# CUTTER.net
KiCad netlist of a schematic drawn in EAGLE
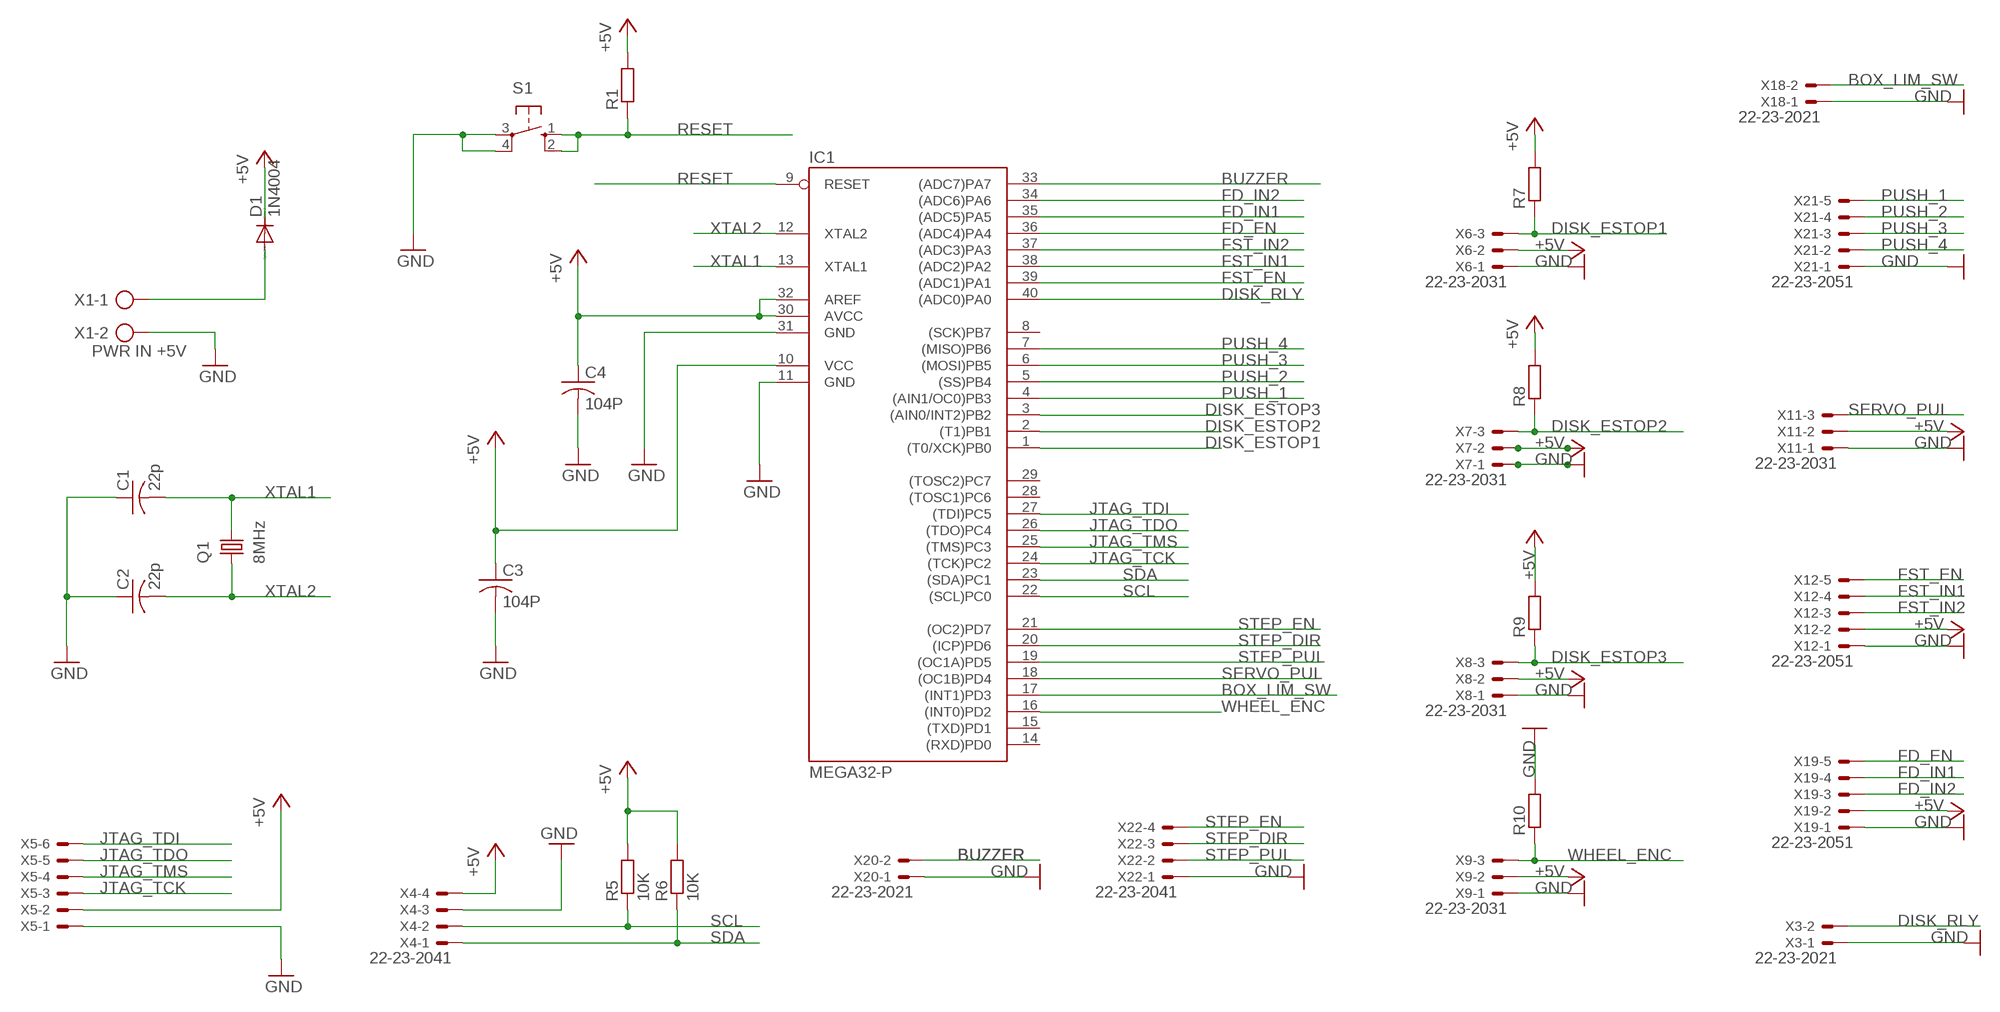
[diagram p0: schematic, sheet 1]

(export (version "E")
  (design (tool "Eeschema 10.0.6"))
  (components
    (comp (ref "C1")
      (value "22p")
      (footprint "eagle-import:C025-025X050")
      (libsource (lib "eagle-import") (part "C-US025-025X050"))
    )
    (comp (ref "C2")
      (value "22p")
      (footprint "eagle-import:C025-025X050")
      (libsource (lib "eagle-import") (part "C-US025-025X050"))
    )
    (comp (ref "C3")
      (value "104P")
      (footprint "eagle-import:C025-025X050")
      (libsource (lib "eagle-import") (part "C-US025-025X050"))
    )
    (comp (ref "C4")
      (value "104P")
      (footprint "eagle-import:C025-025X050")
      (libsource (lib "eagle-import") (part "C-US025-025X050"))
    )
    (comp (ref "D1")
      (value "1N4004")
      (footprint "eagle-import:DO41-10")
      (libsource (lib "eagle-import") (part "1N4004"))
    )
    (comp (ref "IC1")
      (value "MEGA32-P")
      (footprint "eagle-import:DIL40")
      (fields (field (name "MPN") "ATMEGA32-16PU"))
      (libsource (lib "eagle-import") (part "MEGA32-P"))
    )
    (comp (ref "Q1")
      (value "8MHz")
      (footprint "eagle-import:HC49_S")
      (libsource (lib "eagle-import") (part "CRYSTALHC49S"))
    )
    (comp (ref "R1")
      (value "R-EU_0207/10")
      (footprint "eagle-import:0207_10")
      (libsource (lib "eagle-import") (part "R-EU_0207/10"))
    )
    (comp (ref "R5")
      (value "10K")
      (footprint "eagle-import:0207_10")
      (libsource (lib "eagle-import") (part "R-EU_0207/10"))
    )
    (comp (ref "R6")
      (value "10K")
      (footprint "eagle-import:0207_10")
      (libsource (lib "eagle-import") (part "R-EU_0207/10"))
    )
    (comp (ref "R7")
      (value "R-EU_0207/10")
      (footprint "eagle-import:0207_10")
      (libsource (lib "eagle-import") (part "R-EU_0207/10"))
    )
    (comp (ref "R8")
      (value "R-EU_0207/10")
      (footprint "eagle-import:0207_10")
      (libsource (lib "eagle-import") (part "R-EU_0207/10"))
    )
    (comp (ref "R9")
      (value "R-EU_0207/10")
      (footprint "eagle-import:0207_10")
      (libsource (lib "eagle-import") (part "R-EU_0207/10"))
    )
    (comp (ref "R10")
      (value "R-EU_0207/10")
      (footprint "eagle-import:0207_10")
      (libsource (lib "eagle-import") (part "R-EU_0207/10"))
    )
    (comp (ref "S1")
      (value "10-XX")
      (footprint "eagle-import:B3F-10XX")
      (fields (field (name "MPN") "B3F-1000"))
      (libsource (lib "eagle-import") (part "10-XX"))
    )
    (comp (ref "X1")
      (value "PWR IN +5V")
      (footprint "eagle-import:AK500_2")
      (fields (field (name "SPICEPREFIX") "X"))
      (libsource (lib "eagle-import") (part "AK500/2"))
    )
    (comp (ref "X3")
      (value "22-23-2021")
      (footprint "eagle-import:22-23-2021")
      (fields (field (name "MF") "MOLEX"))
      (libsource (lib "eagle-import") (part "22-23-2021"))
    )
    (comp (ref "X4")
      (value "22-23-2041")
      (footprint "eagle-import:22-23-2041")
      (fields (field (name "MF") "MOLEX"))
      (libsource (lib "eagle-import") (part "22-23-2041"))
    )
    (comp (ref "X5")
      (value "22-23-2061")
      (footprint "eagle-import:22-23-2061")
      (fields (field (name "MF") "MOLEX"))
      (libsource (lib "eagle-import") (part "22-23-2061"))
    )
    (comp (ref "X6")
      (value "22-23-2031")
      (footprint "eagle-import:22-23-2031")
      (fields (field (name "MF") "MOLEX"))
      (libsource (lib "eagle-import") (part "22-23-2031"))
    )
    (comp (ref "X7")
      (value "22-23-2031")
      (footprint "eagle-import:22-23-2031")
      (fields (field (name "MF") "MOLEX"))
      (libsource (lib "eagle-import") (part "22-23-2031"))
    )
    (comp (ref "X8")
      (value "22-23-2031")
      (footprint "eagle-import:22-23-2031")
      (fields (field (name "MF") "MOLEX"))
      (libsource (lib "eagle-import") (part "22-23-2031"))
    )
    (comp (ref "X9")
      (value "22-23-2031")
      (footprint "eagle-import:22-23-2031")
      (fields (field (name "MF") "MOLEX"))
      (libsource (lib "eagle-import") (part "22-23-2031"))
    )
    (comp (ref "X11")
      (value "22-23-2031")
      (footprint "eagle-import:22-23-2031")
      (fields (field (name "MF") "MOLEX"))
      (libsource (lib "eagle-import") (part "22-23-2031"))
    )
    (comp (ref "X12")
      (value "22-23-2051")
      (footprint "eagle-import:22-23-2051")
      (fields (field (name "MF") "MOLEX"))
      (libsource (lib "eagle-import") (part "22-23-2051"))
    )
    (comp (ref "X18")
      (value "22-23-2021")
      (footprint "eagle-import:22-23-2021")
      (fields (field (name "MF") "MOLEX"))
      (libsource (lib "eagle-import") (part "22-23-2021"))
    )
    (comp (ref "X19")
      (value "22-23-2051")
      (footprint "eagle-import:22-23-2051")
      (fields (field (name "MF") "MOLEX"))
      (libsource (lib "eagle-import") (part "22-23-2051"))
    )
    (comp (ref "X20")
      (value "22-23-2021")
      (footprint "eagle-import:22-23-2021")
      (fields (field (name "MF") "MOLEX"))
      (libsource (lib "eagle-import") (part "22-23-2021"))
    )
    (comp (ref "X21")
      (value "22-23-2051")
      (footprint "eagle-import:22-23-2051")
      (fields (field (name "MF") "MOLEX"))
      (libsource (lib "eagle-import") (part "22-23-2051"))
    )
    (comp (ref "X22")
      (value "22-23-2041")
      (footprint "eagle-import:22-23-2041")
      (fields (field (name "MF") "MOLEX"))
      (libsource (lib "eagle-import") (part "22-23-2041"))
    )
  )
  (nets
    (net (code "1") (name "+5V") (class "Default")
      (node (ref "C3") (pin "1") (pinfunction "1_1") (pintype "passive"))
      (node (ref "C4") (pin "1") (pinfunction "1_1") (pintype "passive"))
      (node (ref "D1") (pin "C") (pinfunction "C_C") (pintype "passive"))
      (node (ref "IC1") (pin "10") (pinfunction "VCC_10") (pintype "power_in"))
      (node (ref "IC1") (pin "30") (pinfunction "AVCC_30") (pintype "power_in"))
      (node (ref "IC1") (pin "32") (pinfunction "AREF_32") (pintype "passive"))
      (node (ref "R1") (pin "2") (pinfunction "2_2") (pintype "passive"))
      (node (ref "R5") (pin "2") (pinfunction "2_2") (pintype "passive"))
      (node (ref "R6") (pin "2") (pinfunction "2_2") (pintype "passive"))
      (node (ref "R7") (pin "2") (pinfunction "2_2") (pintype "passive"))
      (node (ref "R8") (pin "2") (pinfunction "2_2") (pintype "passive"))
      (node (ref "R9") (pin "2") (pinfunction "2_2") (pintype "passive"))
      (node (ref "X11") (pin "2") (pinfunction "S_2") (pintype "passive"))
      (node (ref "X12") (pin "2") (pinfunction "S_2") (pintype "passive"))
      (node (ref "X19") (pin "2") (pinfunction "S_2") (pintype "passive"))
      (node (ref "X4") (pin "4") (pinfunction "S_4") (pintype "passive"))
      (node (ref "X5") (pin "2") (pinfunction "S_2") (pintype "passive"))
      (node (ref "X6") (pin "2") (pinfunction "S_2") (pintype "passive"))
      (node (ref "X7") (pin "2") (pinfunction "S_2") (pintype "passive"))
      (node (ref "X8") (pin "2") (pinfunction "S_2") (pintype "passive"))
      (node (ref "X9") (pin "2") (pinfunction "S_2") (pintype "passive"))
    )
    (net (code "2") (name "/BOX_LIM_SW") (class "Default")
      (node (ref "IC1") (pin "17") (pinfunction "(INT1)PD3_17") (pintype "bidirectional"))
      (node (ref "X18") (pin "2") (pinfunction "S_2") (pintype "passive"))
    )
    (net (code "3") (name "/BUZZER") (class "Default")
      (node (ref "IC1") (pin "33") (pinfunction "(ADC7)PA7_33") (pintype "bidirectional"))
      (node (ref "X20") (pin "2") (pinfunction "S_2") (pintype "passive"))
    )
    (net (code "4") (name "/DISK_ESTOP1") (class "Default")
      (node (ref "IC1") (pin "1") (pinfunction "(T0/XCK)PB0_1") (pintype "bidirectional"))
      (node (ref "R7") (pin "1") (pinfunction "1_1") (pintype "passive"))
      (node (ref "X6") (pin "3") (pinfunction "S_3") (pintype "passive"))
    )
    (net (code "5") (name "/DISK_ESTOP2") (class "Default")
      (node (ref "IC1") (pin "2") (pinfunction "(T1)PB1_2") (pintype "bidirectional"))
      (node (ref "R8") (pin "1") (pinfunction "1_1") (pintype "passive"))
      (node (ref "X7") (pin "3") (pinfunction "S_3") (pintype "passive"))
    )
    (net (code "6") (name "/DISK_ESTOP3") (class "Default")
      (node (ref "IC1") (pin "3") (pinfunction "(AIN0/INT2)PB2_3") (pintype "bidirectional"))
      (node (ref "R9") (pin "1") (pinfunction "1_1") (pintype "passive"))
      (node (ref "X8") (pin "3") (pinfunction "S_3") (pintype "passive"))
    )
    (net (code "7") (name "/DISK_RLY") (class "Default")
      (node (ref "IC1") (pin "40") (pinfunction "(ADC0)PA0_40") (pintype "bidirectional"))
      (node (ref "X3") (pin "2") (pinfunction "S_2") (pintype "passive"))
    )
    (net (code "8") (name "/FD_EN") (class "Default")
      (node (ref "IC1") (pin "36") (pinfunction "(ADC4)PA4_36") (pintype "bidirectional"))
      (node (ref "X19") (pin "5") (pinfunction "S_5") (pintype "passive"))
    )
    (net (code "9") (name "/FD_IN1") (class "Default")
      (node (ref "IC1") (pin "35") (pinfunction "(ADC5)PA5_35") (pintype "bidirectional"))
      (node (ref "X19") (pin "4") (pinfunction "S_4") (pintype "passive"))
    )
    (net (code "10") (name "/FD_IN2") (class "Default")
      (node (ref "IC1") (pin "34") (pinfunction "(ADC6)PA6_34") (pintype "bidirectional"))
      (node (ref "X19") (pin "3") (pinfunction "S_3") (pintype "passive"))
    )
    (net (code "11") (name "/FST_EN") (class "Default")
      (node (ref "IC1") (pin "39") (pinfunction "(ADC1)PA1_39") (pintype "bidirectional"))
      (node (ref "X12") (pin "5") (pinfunction "S_5") (pintype "passive"))
    )
    (net (code "12") (name "/FST_IN1") (class "Default")
      (node (ref "IC1") (pin "38") (pinfunction "(ADC2)PA2_38") (pintype "bidirectional"))
      (node (ref "X12") (pin "4") (pinfunction "S_4") (pintype "passive"))
    )
    (net (code "13") (name "/FST_IN2") (class "Default")
      (node (ref "IC1") (pin "37") (pinfunction "(ADC3)PA3_37") (pintype "bidirectional"))
      (node (ref "X12") (pin "3") (pinfunction "S_3") (pintype "passive"))
    )
    (net (code "14") (name "/JTAG_TCK") (class "Default")
      (node (ref "IC1") (pin "24") (pinfunction "(TCK)PC2_24") (pintype "bidirectional"))
      (node (ref "X5") (pin "3") (pinfunction "S_3") (pintype "passive"))
    )
    (net (code "15") (name "/JTAG_TDI") (class "Default")
      (node (ref "IC1") (pin "27") (pinfunction "(TDI)PC5_27") (pintype "bidirectional"))
      (node (ref "X5") (pin "6") (pinfunction "S_6") (pintype "passive"))
    )
    (net (code "16") (name "/JTAG_TDO") (class "Default")
      (node (ref "IC1") (pin "26") (pinfunction "(TDO)PC4_26") (pintype "bidirectional"))
      (node (ref "X5") (pin "5") (pinfunction "S_5") (pintype "passive"))
    )
    (net (code "17") (name "/JTAG_TMS") (class "Default")
      (node (ref "IC1") (pin "25") (pinfunction "(TMS)PC3_25") (pintype "bidirectional"))
      (node (ref "X5") (pin "4") (pinfunction "S_4") (pintype "passive"))
    )
    (net (code "18") (name "/PUSH_1") (class "Default")
      (node (ref "IC1") (pin "4") (pinfunction "(AIN1/OC0)PB3_4") (pintype "bidirectional"))
      (node (ref "X21") (pin "5") (pinfunction "S_5") (pintype "passive"))
    )
    (net (code "19") (name "/PUSH_2") (class "Default")
      (node (ref "IC1") (pin "5") (pinfunction "(SS)PB4_5") (pintype "bidirectional"))
      (node (ref "X21") (pin "4") (pinfunction "S_4") (pintype "passive"))
    )
    (net (code "20") (name "/PUSH_3") (class "Default")
      (node (ref "IC1") (pin "6") (pinfunction "(MOSI)PB5_6") (pintype "bidirectional"))
      (node (ref "X21") (pin "3") (pinfunction "S_3") (pintype "passive"))
    )
    (net (code "21") (name "/PUSH_4") (class "Default")
      (node (ref "IC1") (pin "7") (pinfunction "(MISO)PB6_7") (pintype "bidirectional"))
      (node (ref "X21") (pin "2") (pinfunction "S_2") (pintype "passive"))
    )
    (net (code "22") (name "/RESET") (class "Default")
      (node (ref "IC1") (pin "9") (pinfunction "RESET_9") (pintype "input"))
      (node (ref "R1") (pin "1") (pinfunction "1_1") (pintype "passive"))
      (node (ref "S1") (pin "1") (pinfunction "S_1") (pintype "passive"))
      (node (ref "S1") (pin "2") (pinfunction "S1_2") (pintype "passive"))
    )
    (net (code "23") (name "/SCL") (class "Default")
      (node (ref "IC1") (pin "22") (pinfunction "(SCL)PC0_22") (pintype "bidirectional"))
      (node (ref "R5") (pin "1") (pinfunction "1_1") (pintype "passive"))
      (node (ref "X4") (pin "2") (pinfunction "S_2") (pintype "passive"))
    )
    (net (code "24") (name "/SDA") (class "Default")
      (node (ref "IC1") (pin "23") (pinfunction "(SDA)PC1_23") (pintype "bidirectional"))
      (node (ref "R6") (pin "1") (pinfunction "1_1") (pintype "passive"))
      (node (ref "X4") (pin "1") (pinfunction "S_1") (pintype "passive"))
    )
    (net (code "25") (name "/SERVO_PUL") (class "Default")
      (node (ref "IC1") (pin "18") (pinfunction "(OC1B)PD4_18") (pintype "bidirectional"))
      (node (ref "X11") (pin "3") (pinfunction "S_3") (pintype "passive"))
    )
    (net (code "26") (name "/STEP_DIR") (class "Default")
      (node (ref "IC1") (pin "20") (pinfunction "(ICP)PD6_20") (pintype "bidirectional"))
      (node (ref "X22") (pin "3") (pinfunction "S_3") (pintype "passive"))
    )
    (net (code "27") (name "/STEP_EN") (class "Default")
      (node (ref "IC1") (pin "21") (pinfunction "(OC2)PD7_21") (pintype "bidirectional"))
      (node (ref "X22") (pin "4") (pinfunction "S_4") (pintype "passive"))
    )
    (net (code "28") (name "/STEP_PUL") (class "Default")
      (node (ref "IC1") (pin "19") (pinfunction "(OC1A)PD5_19") (pintype "bidirectional"))
      (node (ref "X22") (pin "2") (pinfunction "S_2") (pintype "passive"))
    )
    (net (code "29") (name "/WHEEL_ENC") (class "Default")
      (node (ref "IC1") (pin "16") (pinfunction "(INT0)PD2_16") (pintype "bidirectional"))
      (node (ref "R10") (pin "1") (pinfunction "1_1") (pintype "passive"))
      (node (ref "X9") (pin "3") (pinfunction "S_3") (pintype "passive"))
    )
    (net (code "30") (name "/XTAL1") (class "Default")
      (node (ref "C1") (pin "2") (pinfunction "2_2") (pintype "passive"))
      (node (ref "IC1") (pin "13") (pinfunction "XTAL1_13") (pintype "bidirectional"))
      (node (ref "Q1") (pin "2") (pinfunction "2_2") (pintype "passive"))
    )
    (net (code "31") (name "/XTAL2") (class "Default")
      (node (ref "C2") (pin "2") (pinfunction "2_2") (pintype "passive"))
      (node (ref "IC1") (pin "12") (pinfunction "XTAL2_12") (pintype "bidirectional"))
      (node (ref "Q1") (pin "1") (pinfunction "1_1") (pintype "passive"))
    )
    (net (code "32") (name "GND") (class "Default")
      (node (ref "C1") (pin "1") (pinfunction "1_1") (pintype "passive"))
      (node (ref "C2") (pin "1") (pinfunction "1_1") (pintype "passive"))
      (node (ref "C3") (pin "2") (pinfunction "2_2") (pintype "passive"))
      (node (ref "C4") (pin "2") (pinfunction "2_2") (pintype "passive"))
      (node (ref "IC1") (pin "11") (pinfunction "GND_11") (pintype "power_in"))
      (node (ref "IC1") (pin "31") (pinfunction "GND_31") (pintype "power_in"))
      (node (ref "R10") (pin "2") (pinfunction "2_2") (pintype "passive"))
      (node (ref "S1") (pin "3") (pinfunction "P_3") (pintype "passive"))
      (node (ref "S1") (pin "4") (pinfunction "P1_4") (pintype "passive"))
      (node (ref "X1") (pin "2") (pinfunction "KL_2") (pintype "passive"))
      (node (ref "X11") (pin "1") (pinfunction "S_1") (pintype "passive"))
      (node (ref "X12") (pin "1") (pinfunction "S_1") (pintype "passive"))
      (node (ref "X18") (pin "1") (pinfunction "S_1") (pintype "passive"))
      (node (ref "X19") (pin "1") (pinfunction "S_1") (pintype "passive"))
      (node (ref "X20") (pin "1") (pinfunction "S_1") (pintype "passive"))
      (node (ref "X21") (pin "1") (pinfunction "S_1") (pintype "passive"))
      (node (ref "X22") (pin "1") (pinfunction "S_1") (pintype "passive"))
      (node (ref "X3") (pin "1") (pinfunction "S_1") (pintype "passive"))
      (node (ref "X4") (pin "3") (pinfunction "S_3") (pintype "passive"))
      (node (ref "X5") (pin "1") (pinfunction "S_1") (pintype "passive"))
      (node (ref "X6") (pin "1") (pinfunction "S_1") (pintype "passive"))
      (node (ref "X7") (pin "1") (pinfunction "S_1") (pintype "passive"))
      (node (ref "X8") (pin "1") (pinfunction "S_1") (pintype "passive"))
      (node (ref "X9") (pin "1") (pinfunction "S_1") (pintype "passive"))
    )
    (net (code "33") (name "Net-(X1A-KL)") (class "Default")
      (node (ref "D1") (pin "A") (pinfunction "A_A") (pintype "passive"))
      (node (ref "X1") (pin "1") (pinfunction "KL_1") (pintype "passive"))
    )
    (net (code "34") (name "unconnected-(IC1-(RXD)PD0-Pad14)") (class "Default")
      (node (ref "IC1") (pin "14") (pinfunction "(RXD)PD0_14") (pintype "bidirectional"))
    )
    (net (code "35") (name "unconnected-(IC1-(SCK)PB7-Pad8)") (class "Default")
      (node (ref "IC1") (pin "8") (pinfunction "(SCK)PB7_8") (pintype "bidirectional"))
    )
    (net (code "36") (name "unconnected-(IC1-(TOSC1)PC6-Pad28)") (class "Default")
      (node (ref "IC1") (pin "28") (pinfunction "(TOSC1)PC6_28") (pintype "bidirectional"))
    )
    (net (code "37") (name "unconnected-(IC1-(TOSC2)PC7-Pad29)") (class "Default")
      (node (ref "IC1") (pin "29") (pinfunction "(TOSC2)PC7_29") (pintype "bidirectional"))
    )
    (net (code "38") (name "unconnected-(IC1-(TXD)PD1-Pad15)") (class "Default")
      (node (ref "IC1") (pin "15") (pinfunction "(TXD)PD1_15") (pintype "bidirectional"))
    )
  )
)
